# reflow_oven.net
KiCad netlist of a schematic drawn in EAGLE
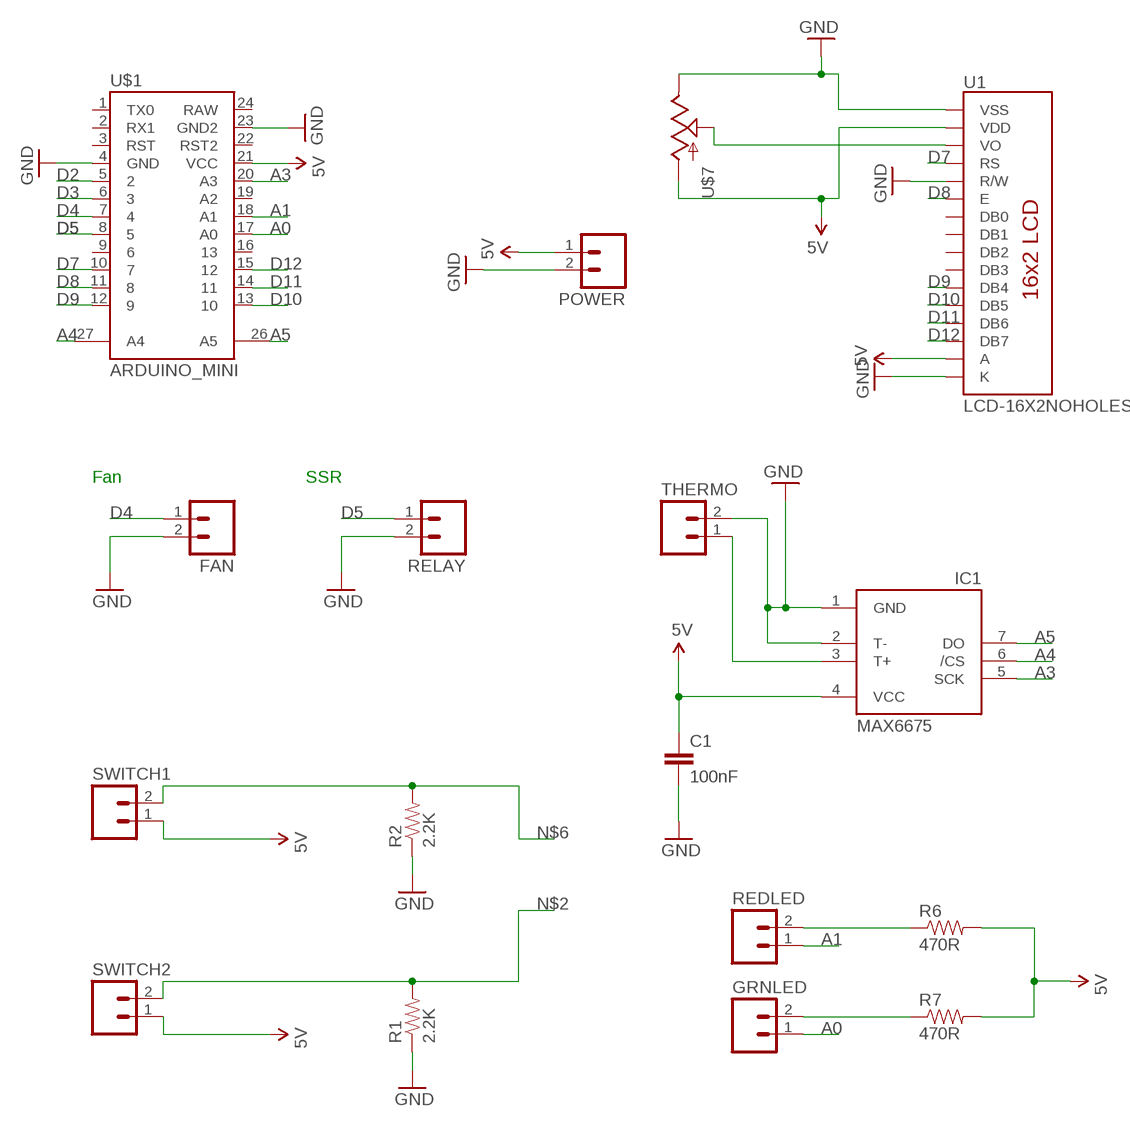
[diagram p0: schematic, sheet 1]

(export (version "E")
  (design (tool "Eeschema 10.0.6"))
  (components
    (comp (ref "C1")
      (value "100nF")
      (footprint "eagle-import:0805")
      (libsource (lib "eagle-import") (part "CAP0805"))
    )
    (comp (ref "FAN")
      (value "M02PTH3")
      (footprint "eagle-import:1X02_LONGPADS")
      (libsource (lib "eagle-import") (part "M02PTH3"))
    )
    (comp (ref "GRNLED")
      (value "M021X02_NO_SILK")
      (footprint "eagle-import:1X02_NO_SILK")
      (libsource (lib "eagle-import") (part "M021X02_NO_SILK"))
    )
    (comp (ref "IC1")
      (value "MAX6675")
      (footprint "eagle-import:SO08")
      (libsource (lib "eagle-import") (part "MAX6675"))
    )
    (comp (ref "POWER")
      (value "M02PTH3")
      (footprint "eagle-import:1X02_LONGPADS")
      (libsource (lib "eagle-import") (part "M02PTH3"))
    )
    (comp (ref "R1")
      (value "2.2K")
      (footprint "eagle-import:0805")
      (libsource (lib "eagle-import") (part "RESISTOR0805-RES"))
    )
    (comp (ref "R2")
      (value "2.2K")
      (footprint "eagle-import:0805")
      (libsource (lib "eagle-import") (part "RESISTOR0805-RES"))
    )
    (comp (ref "R6")
      (value "470R")
      (footprint "eagle-import:0805")
      (libsource (lib "eagle-import") (part "RESISTOR0805-RES"))
    )
    (comp (ref "R7")
      (value "470R")
      (footprint "eagle-import:0805")
      (libsource (lib "eagle-import") (part "RESISTOR0805-RES"))
    )
    (comp (ref "REDLED")
      (value "M021X02_NO_SILK")
      (footprint "eagle-import:1X02_NO_SILK")
      (libsource (lib "eagle-import") (part "M021X02_NO_SILK"))
    )
    (comp (ref "RELAY")
      (value "M02PTH3")
      (footprint "eagle-import:1X02_LONGPADS")
      (libsource (lib "eagle-import") (part "M02PTH3"))
    )
    (comp (ref "SWITCH1")
      (value "M02PTH3")
      (footprint "eagle-import:1X02_LONGPADS")
      (libsource (lib "eagle-import") (part "M02PTH3"))
    )
    (comp (ref "SWITCH2")
      (value "M02PTH3")
      (footprint "eagle-import:1X02_LONGPADS")
      (libsource (lib "eagle-import") (part "M02PTH3"))
    )
    (comp (ref "THERMO")
      (value "M02PTH3")
      (footprint "eagle-import:1X02_LONGPADS")
      (libsource (lib "eagle-import") (part "M02PTH3"))
    )
    (comp (ref "U$1")
      (value "ARDUINO_MINI")
      (footprint "eagle-import:ARDUINO_MINI")
      (libsource (lib "eagle-import") (part "ARDUINO_MINI"))
    )
    (comp (ref "U$7")
      (value "POT-RV16AF-20")
      (footprint "eagle-import:POT_ALPHA_RV16AF-20")
      (libsource (lib "eagle-import") (part "POT-RV16AF-20"))
    )
    (comp (ref "U1")
      (value "LCD-16X2NOHOLES")
      (footprint "eagle-import:LCD-16X2_NOHOLES")
      (libsource (lib "eagle-import") (part "LCD-16X2NOHOLES"))
    )
  )
  (nets
    (net (code "1") (name "/A0") (class "Default")
      (node (ref "GRNLED") (pin "1") (pinfunction "1_1") (pintype "passive"))
      (node (ref "U$1") (pin "17") (pinfunction "A0_17") (pintype "bidirectional"))
    )
    (net (code "2") (name "/A1") (class "Default")
      (node (ref "REDLED") (pin "1") (pinfunction "1_1") (pintype "passive"))
      (node (ref "U$1") (pin "18") (pinfunction "A1_18") (pintype "bidirectional"))
    )
    (net (code "3") (name "/A3") (class "Default")
      (node (ref "IC1") (pin "5") (pinfunction "SCK_5") (pintype "input"))
      (node (ref "U$1") (pin "20") (pinfunction "A3_20") (pintype "bidirectional"))
    )
    (net (code "4") (name "/A4") (class "Default")
      (node (ref "IC1") (pin "6") (pinfunction "/CS_6") (pintype "input"))
      (node (ref "U$1") (pin "27") (pinfunction "A4_27") (pintype "bidirectional"))
    )
    (net (code "5") (name "/A5") (class "Default")
      (node (ref "IC1") (pin "7") (pinfunction "DO_7") (pintype "output"))
      (node (ref "U$1") (pin "26") (pinfunction "A5_26") (pintype "bidirectional"))
    )
    (net (code "6") (name "/D2") (class "Default")
      (node (ref "U$1") (pin "5") (pinfunction "2_5") (pintype "bidirectional"))
    )
    (net (code "7") (name "/D3") (class "Default")
      (node (ref "U$1") (pin "6") (pinfunction "3_6") (pintype "bidirectional"))
    )
    (net (code "8") (name "/D4") (class "Default")
      (node (ref "FAN") (pin "1") (pinfunction "1_1") (pintype "passive"))
      (node (ref "U$1") (pin "7") (pinfunction "4_7") (pintype "bidirectional"))
    )
    (net (code "9") (name "/D5") (class "Default")
      (node (ref "RELAY") (pin "1") (pinfunction "1_1") (pintype "passive"))
      (node (ref "U$1") (pin "8") (pinfunction "5_8") (pintype "bidirectional"))
    )
    (net (code "10") (name "/D7") (class "Default")
      (node (ref "U$1") (pin "10") (pinfunction "7_10") (pintype "bidirectional"))
      (node (ref "U1") (pin "4") (pinfunction "RS_4") (pintype "input"))
    )
    (net (code "11") (name "/D8") (class "Default")
      (node (ref "U$1") (pin "11") (pinfunction "8_11") (pintype "bidirectional"))
      (node (ref "U1") (pin "6") (pinfunction "E_6") (pintype "input"))
    )
    (net (code "12") (name "/D9") (class "Default")
      (node (ref "U$1") (pin "12") (pinfunction "9_12") (pintype "bidirectional"))
      (node (ref "U1") (pin "11") (pinfunction "DB4_11") (pintype "bidirectional"))
    )
    (net (code "13") (name "/D10") (class "Default")
      (node (ref "U$1") (pin "13") (pinfunction "10_13") (pintype "bidirectional"))
      (node (ref "U1") (pin "12") (pinfunction "DB5_12") (pintype "bidirectional"))
    )
    (net (code "14") (name "/D11") (class "Default")
      (node (ref "U$1") (pin "14") (pinfunction "11_14") (pintype "bidirectional"))
      (node (ref "U1") (pin "13") (pinfunction "DB6_13") (pintype "bidirectional"))
    )
    (net (code "15") (name "/D12") (class "Default")
      (node (ref "U$1") (pin "15") (pinfunction "12_15") (pintype "bidirectional"))
      (node (ref "U1") (pin "14") (pinfunction "DB7_14") (pintype "bidirectional"))
    )
    (net (code "16") (name "/N$2") (class "Default")
      (node (ref "R1") (pin "2") (pinfunction "2_2") (pintype "passive"))
      (node (ref "SWITCH2") (pin "2") (pinfunction "2_2") (pintype "passive"))
    )
    (net (code "17") (name "/N$6") (class "Default")
      (node (ref "R2") (pin "2") (pinfunction "2_2") (pintype "passive"))
      (node (ref "SWITCH1") (pin "2") (pinfunction "2_2") (pintype "passive"))
    )
    (net (code "18") (name "5V") (class "Default")
      (node (ref "C1") (pin "1") (pinfunction "1_1") (pintype "passive"))
      (node (ref "IC1") (pin "4") (pinfunction "VCC_4") (pintype "power_in"))
      (node (ref "POWER") (pin "1") (pinfunction "1_1") (pintype "passive"))
      (node (ref "R6") (pin "2") (pinfunction "2_2") (pintype "passive"))
      (node (ref "R7") (pin "2") (pinfunction "2_2") (pintype "passive"))
      (node (ref "SWITCH1") (pin "1") (pinfunction "1_1") (pintype "passive"))
      (node (ref "SWITCH2") (pin "1") (pinfunction "1_1") (pintype "passive"))
      (node (ref "U$1") (pin "21") (pinfunction "VCC_21") (pintype "bidirectional"))
      (node (ref "U$7") (pin "1") (pinfunction "A_1") (pintype "passive"))
      (node (ref "U1") (pin "15") (pinfunction "A_15") (pintype "power_in"))
      (node (ref "U1") (pin "2") (pinfunction "VDD_2") (pintype "power_in"))
    )
    (net (code "19") (name "GND") (class "Default")
      (node (ref "C1") (pin "2") (pinfunction "2_2") (pintype "passive"))
      (node (ref "FAN") (pin "2") (pinfunction "2_2") (pintype "passive"))
      (node (ref "IC1") (pin "1") (pinfunction "GND_1") (pintype "power_in"))
      (node (ref "IC1") (pin "2") (pinfunction "T-_2") (pintype "input"))
      (node (ref "POWER") (pin "2") (pinfunction "2_2") (pintype "passive"))
      (node (ref "R1") (pin "1") (pinfunction "1_1") (pintype "passive"))
      (node (ref "R2") (pin "1") (pinfunction "1_1") (pintype "passive"))
      (node (ref "RELAY") (pin "2") (pinfunction "2_2") (pintype "passive"))
      (node (ref "THERMO") (pin "2") (pinfunction "2_2") (pintype "passive"))
      (node (ref "U$1") (pin "23") (pinfunction "GND2_23") (pintype "bidirectional"))
      (node (ref "U$1") (pin "4") (pinfunction "GND_4") (pintype "bidirectional"))
      (node (ref "U$7") (pin "3") (pinfunction "E_3") (pintype "passive"))
      (node (ref "U1") (pin "1") (pinfunction "VSS_1") (pintype "power_in"))
      (node (ref "U1") (pin "16") (pinfunction "K_16") (pintype "power_in"))
      (node (ref "U1") (pin "5") (pinfunction "R/W_5") (pintype "input"))
    )
    (net (code "20") (name "Net-(GRNLED-Pad2)") (class "Default")
      (node (ref "GRNLED") (pin "2") (pinfunction "2_2") (pintype "passive"))
      (node (ref "R7") (pin "1") (pinfunction "1_1") (pintype "passive"))
    )
    (net (code "21") (name "Net-(IC1-T+)") (class "Default")
      (node (ref "IC1") (pin "3") (pinfunction "T+_3") (pintype "input"))
      (node (ref "THERMO") (pin "1") (pinfunction "1_1") (pintype "passive"))
    )
    (net (code "22") (name "Net-(R6-Pad1)") (class "Default")
      (node (ref "R6") (pin "1") (pinfunction "1_1") (pintype "passive"))
      (node (ref "REDLED") (pin "2") (pinfunction "2_2") (pintype "passive"))
    )
    (net (code "23") (name "Net-(U$7-S)") (class "Default")
      (node (ref "U$7") (pin "2") (pinfunction "S_2") (pintype "passive"))
      (node (ref "U1") (pin "3") (pinfunction "VO_3") (pintype "bidirectional"))
    )
    (net (code "24") (name "unconnected-(U$1-6-Pad9)") (class "Default")
      (node (ref "U$1") (pin "9") (pinfunction "6_9") (pintype "bidirectional"))
    )
    (net (code "25") (name "unconnected-(U$1-13-Pad16)") (class "Default")
      (node (ref "U$1") (pin "16") (pinfunction "13_16") (pintype "bidirectional"))
    )
    (net (code "26") (name "unconnected-(U$1-A2-Pad19)") (class "Default")
      (node (ref "U$1") (pin "19") (pinfunction "A2_19") (pintype "bidirectional"))
    )
    (net (code "27") (name "unconnected-(U$1-RAW-Pad24)") (class "Default")
      (node (ref "U$1") (pin "24") (pinfunction "RAW_24") (pintype "bidirectional"))
    )
    (net (code "28") (name "unconnected-(U$1-RST-Pad3)") (class "Default")
      (node (ref "U$1") (pin "3") (pinfunction "RST_3") (pintype "bidirectional"))
    )
    (net (code "29") (name "unconnected-(U$1-RST2-Pad22)") (class "Default")
      (node (ref "U$1") (pin "22") (pinfunction "RST2_22") (pintype "bidirectional"))
    )
    (net (code "30") (name "unconnected-(U$1-RX1-Pad2)") (class "Default")
      (node (ref "U$1") (pin "2") (pinfunction "RX1_2") (pintype "bidirectional"))
    )
    (net (code "31") (name "unconnected-(U$1-TX0-Pad1)") (class "Default")
      (node (ref "U$1") (pin "1") (pinfunction "TX0_1") (pintype "bidirectional"))
    )
    (net (code "32") (name "unconnected-(U1-DB0-Pad7)") (class "Default")
      (node (ref "U1") (pin "7") (pinfunction "DB0_7") (pintype "bidirectional"))
    )
    (net (code "33") (name "unconnected-(U1-DB1-Pad8)") (class "Default")
      (node (ref "U1") (pin "8") (pinfunction "DB1_8") (pintype "bidirectional"))
    )
    (net (code "34") (name "unconnected-(U1-DB2-Pad9)") (class "Default")
      (node (ref "U1") (pin "9") (pinfunction "DB2_9") (pintype "bidirectional"))
    )
    (net (code "35") (name "unconnected-(U1-DB3-Pad10)") (class "Default")
      (node (ref "U1") (pin "10") (pinfunction "DB3_10") (pintype "bidirectional"))
    )
  )
)
